# adc_chanels_b.net
KiCad netlist of a schematic drawn in Altium Designer
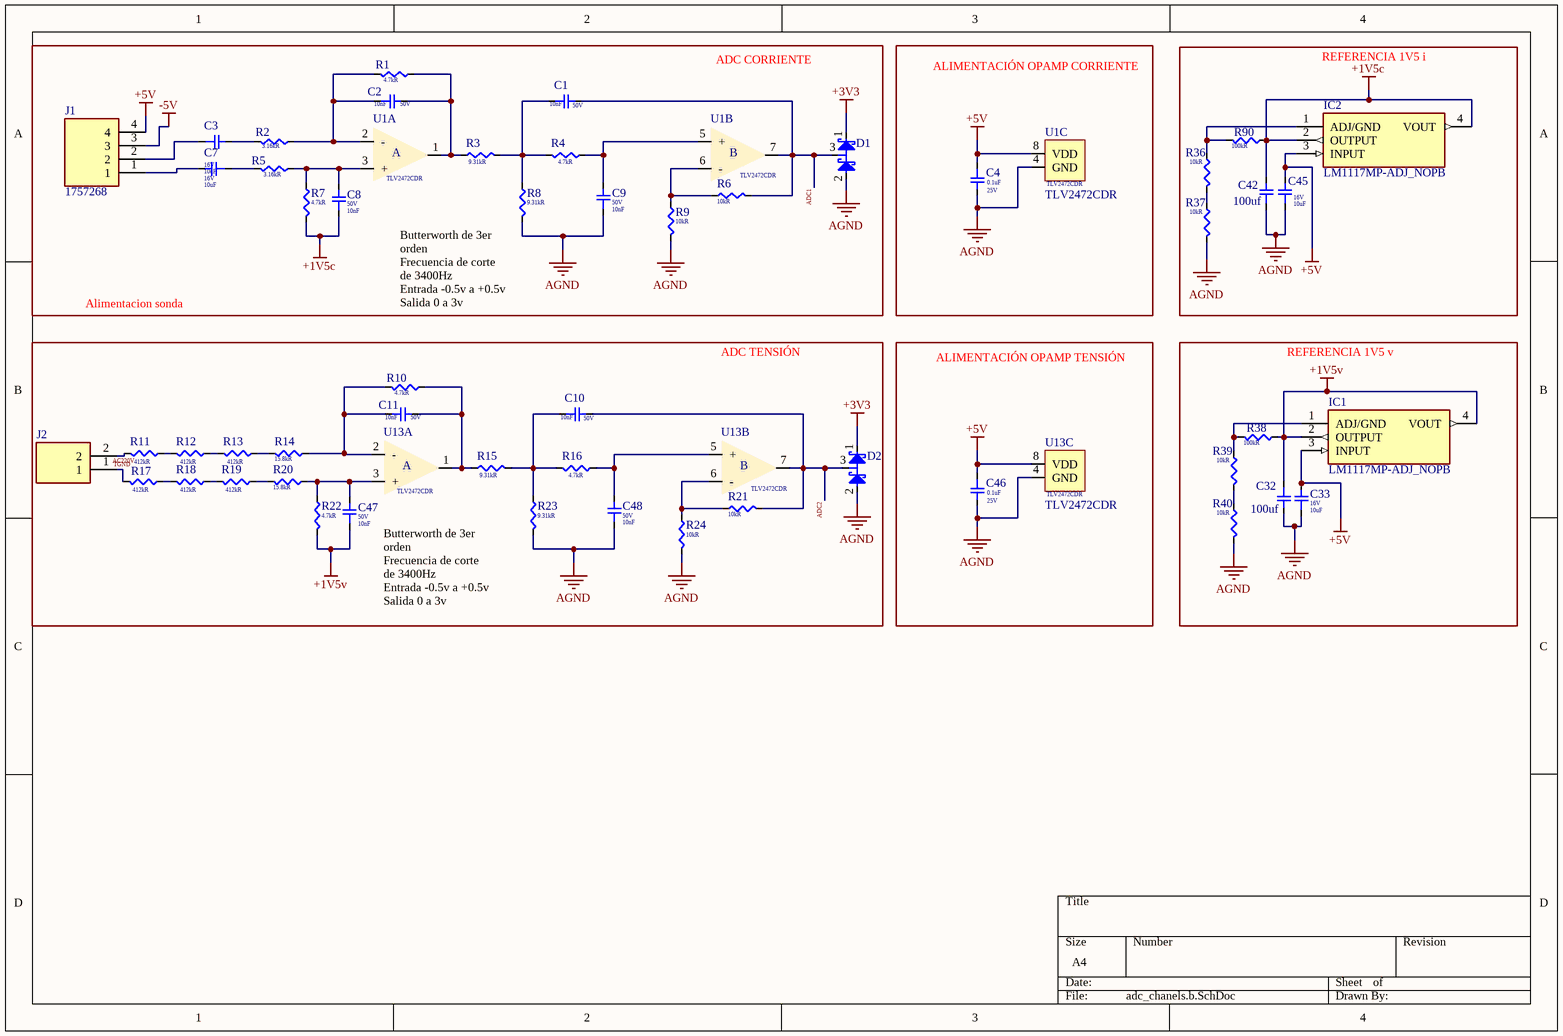
[diagram p0: adc_chanels.b.SchDoc]

(export (version "E")
  (design (tool "Eeschema 10.0.6"))
  (components
    (comp (ref "C1")
      (value "CAP_GRM2195C1H103FA01D_MURATA")
      (footprint "CAP smd 0805 ok")
      (description "0805 10 nF 50 V ±1% Tolerance C0G SMD Multilayer Ceramic Capacitor")
      (fields
        (field (name "TOLERANCE") "1%")
        (field (name "VOLTAGE") "50V")
        (field (name "CAPACITANCE") "10nF")
      )
      (libsource (lib "Cap") (part "CAP_GRM2195C1H103FA01D_MURATA"))
    )
    (comp (ref "C2")
      (value "CAP_GRM2195C1H103FA01D_MURATA")
      (footprint "CAP smd 0805 ok")
      (description "0805 10 nF 50 V ±1% Tolerance C0G SMD Multilayer Ceramic Capacitor")
      (fields
        (field (name "TOLERANCE") "1%")
        (field (name "VOLTAGE") "50V")
        (field (name "CAPACITANCE") "10nF")
      )
      (libsource (lib "Cap") (part "CAP_GRM2195C1H103FA01D_MURATA"))
    )
    (comp (ref "C3")
      (value "CAP_CL21A106KOCL3RC")
      (footprint "CAP smd 0805 OK")
      (description "CAP CER 10UF 16V X5R 0805")
      (fields
        (field (name "TOLERANCE") "10%")
        (field (name "VOLTAGE RATING") "16V")
        (field (name "CAPACITANCE") "10uF")
      )
      (libsource (lib "Cap") (part "CAP_CL21A106KOCL3RC"))
    )
    (comp (ref "C4")
      (value "CAP_CC0805KRX7R8BB104_YAGEO")
      (footprint "CAP smd 0805 ok")
      (description "CAPACITOR, 0805, 100NF, 25V, REEL 4000")
      (fields
        (field (name "TOLERANCE") "10%")
        (field (name "VOLTAGE RATING") "25V")
        (field (name "CAPACITANCE") "0.1uF")
      )
      (libsource (lib "Cap") (part "CAP_CC0805KRX7R8BB104_YAGEO"))
    )
    (comp (ref "C7")
      (value "CAP_CL21A106KOCL3RC")
      (footprint "CAP smd 0805 OK")
      (description "CAP CER 10UF 16V X5R 0805")
      (fields
        (field (name "TOLERANCE") "10%")
        (field (name "VOLTAGE RATING") "16V")
        (field (name "CAPACITANCE") "10uF")
      )
      (libsource (lib "Cap") (part "CAP_CL21A106KOCL3RC"))
    )
    (comp (ref "C8")
      (value "CAP_GRM2195C1H103FA01D_MURATA")
      (footprint "CAP smd 0805 ok")
      (description "0805 10 nF 50 V ±1% Tolerance C0G SMD Multilayer Ceramic Capacitor")
      (fields
        (field (name "TOLERANCE") "1%")
        (field (name "VOLTAGE") "50V")
        (field (name "CAPACITANCE") "10nF")
      )
      (libsource (lib "Cap") (part "CAP_GRM2195C1H103FA01D_MURATA"))
    )
    (comp (ref "C9")
      (value "CAP_GRM2195C1H103FA01D_MURATA")
      (footprint "CAP smd 0805 ok")
      (description "0805 10 nF 50 V ±1% Tolerance C0G SMD Multilayer Ceramic Capacitor")
      (fields
        (field (name "TOLERANCE") "1%")
        (field (name "VOLTAGE") "50V")
        (field (name "CAPACITANCE") "10nF")
      )
      (libsource (lib "Cap") (part "CAP_GRM2195C1H103FA01D_MURATA"))
    )
    (comp (ref "C10")
      (value "CAP_GRM2195C1H103FA01D_MURATA")
      (footprint "CAP smd 0805 ok")
      (description "0805 10 nF 50 V ±1% Tolerance C0G SMD Multilayer Ceramic Capacitor")
      (fields
        (field (name "TOLERANCE") "1%")
        (field (name "VOLTAGE") "50V")
        (field (name "CAPACITANCE") "10nF")
      )
      (libsource (lib "Cap") (part "CAP_GRM2195C1H103FA01D_MURATA"))
    )
    (comp (ref "C11")
      (value "CAP_GRM2195C1H103FA01D_MURATA")
      (footprint "CAP smd 0805 ok")
      (description "0805 10 nF 50 V ±1% Tolerance C0G SMD Multilayer Ceramic Capacitor")
      (fields
        (field (name "TOLERANCE") "1%")
        (field (name "VOLTAGE") "50V")
        (field (name "CAPACITANCE") "10nF")
      )
      (libsource (lib "Cap") (part "CAP_GRM2195C1H103FA01D_MURATA"))
    )
    (comp (ref "C32")
      (value "100uf")
      (footprint "Cap 100uf")
      (libsource (lib "Cap") (part "CAP 100uf murata"))
    )
    (comp (ref "C33")
      (value "CAP_CL21A106KOCL3RC")
      (footprint "CAP smd 0805 OK")
      (description "CAP CER 10UF 16V X5R 0805")
      (fields
        (field (name "TOLERANCE") "10%")
        (field (name "VOLTAGE RATING") "16V")
        (field (name "CAPACITANCE") "10uF")
      )
      (libsource (lib "Cap") (part "CAP_CL21A106KOCL3RC"))
    )
    (comp (ref "C42")
      (value "100uf")
      (footprint "Cap 100uf")
      (libsource (lib "Cap") (part "CAP 100uf murata"))
    )
    (comp (ref "C45")
      (value "CAP_CL21A106KOCL3RC")
      (footprint "CAP smd 0805 OK")
      (description "CAP CER 10UF 16V X5R 0805")
      (fields
        (field (name "TOLERANCE") "10%")
        (field (name "VOLTAGE RATING") "16V")
        (field (name "CAPACITANCE") "10uF")
      )
      (libsource (lib "Cap") (part "CAP_CL21A106KOCL3RC"))
    )
    (comp (ref "C46")
      (value "CAP_CC0805KRX7R8BB104_YAGEO")
      (footprint "CAP smd 0805 ok")
      (description "CAPACITOR, 0805, 100NF, 25V, REEL 4000")
      (fields
        (field (name "TOLERANCE") "10%")
        (field (name "VOLTAGE RATING") "25V")
        (field (name "CAPACITANCE") "0.1uF")
      )
      (libsource (lib "Cap") (part "CAP_CC0805KRX7R8BB104_YAGEO"))
    )
    (comp (ref "C47")
      (value "CAP_GRM2195C1H103FA01D_MURATA")
      (footprint "CAP smd 0805 ok")
      (description "0805 10 nF 50 V ±1% Tolerance C0G SMD Multilayer Ceramic Capacitor")
      (fields
        (field (name "TOLERANCE") "1%")
        (field (name "VOLTAGE") "50V")
        (field (name "CAPACITANCE") "10nF")
      )
      (libsource (lib "Cap") (part "CAP_GRM2195C1H103FA01D_MURATA"))
    )
    (comp (ref "C48")
      (value "CAP_GRM2195C1H103FA01D_MURATA")
      (footprint "CAP smd 0805 ok")
      (description "0805 10 nF 50 V ±1% Tolerance C0G SMD Multilayer Ceramic Capacitor")
      (fields
        (field (name "TOLERANCE") "1%")
        (field (name "VOLTAGE") "50V")
        (field (name "CAPACITANCE") "10nF")
      )
      (libsource (lib "Cap") (part "CAP_GRM2195C1H103FA01D_MURATA"))
    )
    (comp (ref "D1")
      (value "BAS40-04-TP")
      (footprint "diode shockit ok")
      (description "DIODE ARRAY SCHOTTKY 40V SOT23")
      (libsource (lib "diode") (part "BAS40-04-TP"))
    )
    (comp (ref "D2")
      (value "BAS40-04-TP")
      (footprint "diode shockit ok")
      (description "DIODE ARRAY SCHOTTKY 40V SOT23")
      (libsource (lib "diode") (part "BAS40-04-TP"))
    )
    (comp (ref "IC1")
      (value "LM1117MP-ADJ_NOPB")
      (footprint "SamacSys:SOT230P700X180-4N")
      (description "Integrated Circuit")
      (fields
        (field (name "MANUFACTURER_PART_NUMBER") "LM1117MP-ADJ/NOPB")
        (field (name "MOUSER PART NUMBER") "926-LM1117MP-ADJNOPB")
      )
      (libsource (lib "*") (part "LM1117MP-ADJ_NOPB"))
    )
    (comp (ref "IC2")
      (value "LM1117MP-ADJ_NOPB")
      (footprint "SamacSys:SOT230P700X180-4N")
      (description "Integrated Circuit")
      (fields
        (field (name "MANUFACTURER_PART_NUMBER") "LM1117MP-ADJ/NOPB")
        (field (name "MOUSER PART NUMBER") "926-LM1117MP-ADJNOPB")
      )
      (libsource (lib "*") (part "LM1117MP-ADJ_NOPB"))
    )
    (comp (ref "J1")
      (value "1757268")
      (footprint "SamacSys:1757268")
      (description "Connector")
      (fields (field (name "MOUSER PART NUMBER") "651-1757268"))
      (libsource (lib "*") (part "1757268"))
    )
    (comp (ref "J2")
      (value "1757242")
      (footprint "SamacSys:1757242")
      (description "Connector")
      (fields (field (name "MOUSER PART NUMBER") "651-1757242"))
      (libsource (lib "*") (part "1757242"))
    )
    (comp (ref "R1")
      (value "RC0805FR-074K7L")
      (footprint "res 0805 ok")
      (description "YAGEO - RC0805FR-074K7L - SMD  0805 [2012 Metric], 4.7 kohm,  125 mW")
      (fields (field (name "TOLERANCE") "1%") (field (name "RESISTANCE") "4.7kR"))
      (libsource (lib "res") (part "RC0805FR-074K7L"))
    )
    (comp (ref "R2")
      (value "RC0805FR-073K16L")
      (footprint "res 0805 ok")
      (description "Res Thick Film smd 0805 3.16K Ohm 1% 0.125W(1/8W)")
      (fields (field (name "TOLERANCE") "1%") (field (name "RESISTANCE") "3.16kR"))
      (libsource (lib "res") (part "RC0805FR-073K16L"))
    )
    (comp (ref "R3")
      (value "RC0805FR-079K31L")
      (footprint "res 0805 ok")
      (description "Res Thick Film smd 0805 9.31K Ohm 1% 0.125W(1/8W)")
      (fields (field (name "TOLERANCE") "1%") (field (name "RESISTANCE") "9.31kR"))
      (libsource (lib "res") (part "RC0805FR-079K31L"))
    )
    (comp (ref "R4")
      (value "RC0805FR-074K7L")
      (footprint "res 0805 ok")
      (description "YAGEO - RC0805FR-074K7L - SMD  0805 [2012 Metric], 4.7 kohm,  125 mW")
      (fields (field (name "TOLERANCE") "1%") (field (name "RESISTANCE") "4.7kR"))
      (libsource (lib "res") (part "RC0805FR-074K7L"))
    )
    (comp (ref "R5")
      (value "RC0805FR-073K16L")
      (footprint "res 0805 ok")
      (description "Res Thick Film smd 0805 3.16K Ohm 1% 0.125W(1/8W)")
      (fields (field (name "TOLERANCE") "1%") (field (name "RESISTANCE") "3.16kR"))
      (libsource (lib "res") (part "RC0805FR-073K16L"))
    )
    (comp (ref "R6")
      (value "RC0805FR-0710KL")
      (footprint "res 0805 ok")
      (description "RES SMD  0805 10K OHM 1% 1/8W")
      (fields (field (name "TOLERANCE") "1%") (field (name "RESISTANCE") "10kR"))
      (libsource (lib "res") (part "RC0805FR-0710KL"))
    )
    (comp (ref "R7")
      (value "RC0805FR-074K7L")
      (footprint "res 0805 ok")
      (description "YAGEO - RC0805FR-074K7L - SMD  0805 [2012 Metric], 4.7 kohm,  125 mW")
      (fields (field (name "TOLERANCE") "1%") (field (name "RESISTANCE") "4.7kR"))
      (libsource (lib "res") (part "RC0805FR-074K7L"))
    )
    (comp (ref "R8")
      (value "RC0805FR-079K31L")
      (footprint "res 0805 ok")
      (description "Res Thick Film smd 0805 9.31K Ohm 1% 0.125W(1/8W)")
      (fields (field (name "TOLERANCE") "1%") (field (name "RESISTANCE") "9.31kR"))
      (libsource (lib "res") (part "RC0805FR-079K31L"))
    )
    (comp (ref "R9")
      (value "RC0805FR-0710KL")
      (footprint "res 0805 ok")
      (description "RES SMD  0805 10K OHM 1% 1/8W")
      (fields (field (name "TOLERANCE") "1%") (field (name "RESISTANCE") "10kR"))
      (libsource (lib "res") (part "RC0805FR-0710KL"))
    )
    (comp (ref "R10")
      (value "RC0805FR-074K7L")
      (footprint "res 0805 ok")
      (description "YAGEO - RC0805FR-074K7L - SMD  0805 [2012 Metric], 4.7 kohm,  125 mW")
      (fields (field (name "TOLERANCE") "1%") (field (name "RESISTANCE") "4.7kR"))
      (libsource (lib "res") (part "RC0805FR-074K7L"))
    )
    (comp (ref "R11")
      (value "RC0805FR-07412KL")
      (footprint "res 0805 ok")
      (description "RES SMD 0805 412K OHM 1% 1/8W")
      (fields (field (name "TOLERANCE") "1%") (field (name "RESISTANCE") "412kR"))
      (libsource (lib "res") (part "RC0805FR-07412KL"))
    )
    (comp (ref "R12")
      (value "RC0805FR-07412KL")
      (footprint "res 0805 ok")
      (description "RES SMD 0805 412K OHM 1% 1/8W")
      (fields (field (name "TOLERANCE") "1%") (field (name "RESISTANCE") "412kR"))
      (libsource (lib "res") (part "RC0805FR-07412KL"))
    )
    (comp (ref "R13")
      (value "RC0805FR-07412KL")
      (footprint "res 0805 ok")
      (description "RES SMD 0805 412K OHM 1% 1/8W")
      (fields (field (name "TOLERANCE") "1%") (field (name "RESISTANCE") "412kR"))
      (libsource (lib "res") (part "RC0805FR-07412KL"))
    )
    (comp (ref "R14")
      (value "RC0805FR-0715K8L")
      (footprint "res 0805 ok")
      (description "Res Thick Film smd 0805 15.8K Ohm 1% 0.125W(1/8W)")
      (fields (field (name "TOLERANCE") "1%") (field (name "RESISTANCE") "15.8kR"))
      (libsource (lib "res") (part "RC0805FR-0715K8L"))
    )
    (comp (ref "R15")
      (value "RC0805FR-079K31L")
      (footprint "res 0805 ok")
      (description "Res Thick Film smd 0805 9.31K Ohm 1% 0.125W(1/8W)")
      (fields (field (name "TOLERANCE") "1%") (field (name "RESISTANCE") "9.31kR"))
      (libsource (lib "res") (part "RC0805FR-079K31L"))
    )
    (comp (ref "R16")
      (value "RC0805FR-074K7L")
      (footprint "res 0805 ok")
      (description "YAGEO - RC0805FR-074K7L - SMD  0805 [2012 Metric], 4.7 kohm,  125 mW")
      (fields (field (name "TOLERANCE") "1%") (field (name "RESISTANCE") "4.7kR"))
      (libsource (lib "res") (part "RC0805FR-074K7L"))
    )
    (comp (ref "R17")
      (value "RC0805FR-07412KL")
      (footprint "res 0805 ok")
      (description "RES SMD 0805 412K OHM 1% 1/8W")
      (fields (field (name "TOLERANCE") "1%") (field (name "RESISTANCE") "412kR"))
      (libsource (lib "res") (part "RC0805FR-07412KL"))
    )
    (comp (ref "R18")
      (value "RC0805FR-07412KL")
      (footprint "res 0805 ok")
      (description "RES SMD 0805 412K OHM 1% 1/8W")
      (fields (field (name "TOLERANCE") "1%") (field (name "RESISTANCE") "412kR"))
      (libsource (lib "res") (part "RC0805FR-07412KL"))
    )
    (comp (ref "R19")
      (value "RC0805FR-07412KL")
      (footprint "res 0805 ok")
      (description "RES SMD 0805 412K OHM 1% 1/8W")
      (fields (field (name "TOLERANCE") "1%") (field (name "RESISTANCE") "412kR"))
      (libsource (lib "res") (part "RC0805FR-07412KL"))
    )
    (comp (ref "R20")
      (value "RC0805FR-0715K8L")
      (footprint "res 0805 ok")
      (description "Res Thick Film smd 0805 15.8K Ohm 1% 0.125W(1/8W)")
      (fields (field (name "TOLERANCE") "1%") (field (name "RESISTANCE") "15.8kR"))
      (libsource (lib "res") (part "RC0805FR-0715K8L"))
    )
    (comp (ref "R21")
      (value "RC0805FR-0710KL")
      (footprint "res 0805 ok")
      (description "RES SMD  0805 10K OHM 1% 1/8W")
      (fields (field (name "TOLERANCE") "1%") (field (name "RESISTANCE") "10kR"))
      (libsource (lib "res") (part "RC0805FR-0710KL"))
    )
    (comp (ref "R22")
      (value "RC0805FR-074K7L")
      (footprint "res 0805 ok")
      (description "YAGEO - RC0805FR-074K7L - SMD  0805 [2012 Metric], 4.7 kohm,  125 mW")
      (fields (field (name "TOLERANCE") "1%") (field (name "RESISTANCE") "4.7kR"))
      (libsource (lib "res") (part "RC0805FR-074K7L"))
    )
    (comp (ref "R23")
      (value "RC0805FR-079K31L")
      (footprint "res 0805 ok")
      (description "Res Thick Film smd 0805 9.31K Ohm 1% 0.125W(1/8W)")
      (fields (field (name "TOLERANCE") "1%") (field (name "RESISTANCE") "9.31kR"))
      (libsource (lib "res") (part "RC0805FR-079K31L"))
    )
    (comp (ref "R24")
      (value "RC0805FR-0710KL")
      (footprint "res 0805 ok")
      (description "RES SMD  0805 10K OHM 1% 1/8W")
      (fields (field (name "TOLERANCE") "1%") (field (name "RESISTANCE") "10kR"))
      (libsource (lib "res") (part "RC0805FR-0710KL"))
    )
    (comp (ref "R36")
      (value "RC0805JR-0710KL")
      (footprint "res 0805 ok")
      (description "Res Thick Film smd 0805 10K Ohm 5% 1/8W")
      (fields (field (name "TOLERANCE") "5%") (field (name "RESISTANCE") "10kR"))
      (libsource (lib "res") (part "RC0805JR-0710KL"))
    )
    (comp (ref "R37")
      (value "RC0805JR-0710KL")
      (footprint "res 0805 ok")
      (description "Res Thick Film smd 0805 10K Ohm 5% 1/8W")
      (fields (field (name "TOLERANCE") "5%") (field (name "RESISTANCE") "10kR"))
      (libsource (lib "res") (part "RC0805JR-0710KL"))
    )
    (comp (ref "R38")
      (value "AC0805JR-07100KL")
      (footprint "res 0805 ok")
      (description "Thick Film Resistors - SMD 0805  100K ohm 5% 1/8W")
      (fields (field (name "TOLERANCE") "5%") (field (name "RESISTANCE") "100kR"))
      (libsource (lib "res") (part "AC0805JR-07100KL"))
    )
    (comp (ref "R39")
      (value "RC0805JR-0710KL")
      (footprint "res 0805 ok")
      (description "Res Thick Film smd 0805 10K Ohm 5% 1/8W")
      (fields (field (name "TOLERANCE") "5%") (field (name "RESISTANCE") "10kR"))
      (libsource (lib "res") (part "RC0805JR-0710KL"))
    )
    (comp (ref "R40")
      (value "RC0805JR-0710KL")
      (footprint "res 0805 ok")
      (description "Res Thick Film smd 0805 10K Ohm 5% 1/8W")
      (fields (field (name "TOLERANCE") "5%") (field (name "RESISTANCE") "10kR"))
      (libsource (lib "res") (part "RC0805JR-0710KL"))
    )
    (comp (ref "R90")
      (value "AC0805JR-07100KL")
      (footprint "res 0805 ok")
      (description "Thick Film Resistors - SMD 0805  100K ohm 5% 1/8W")
      (fields (field (name "TOLERANCE") "5%") (field (name "RESISTANCE") "100kR"))
      (libsource (lib "res") (part "AC0805JR-07100KL"))
    )
    (comp (ref "U1")
      (value "TLV2472CDR")
      (footprint "tlv2472 ok")
      (description "IC OPAMP GP 2.8MHZ RRO 8SOIC")
      (libsource (lib "ic") (part "TLV2472CDR"))
    )
    (comp (ref "U13")
      (value "TLV2472CDR")
      (footprint "tlv2472 ok")
      (description "IC OPAMP GP 2.8MHZ RRO 8SOIC")
      (libsource (lib "ic") (part "TLV2472CDR"))
    )
  )
  (nets
    (net (code "1") (name "+1V5c") (class "Default")
      (node (ref "C42") (pin "23") (pinfunction "23_23") (pintype "passive"))
      (node (ref "C8") (pin "23") (pinfunction "23_23") (pintype "passive"))
      (node (ref "IC2") (pin "2") (pinfunction "OUTPUT_2") (pintype "output"))
      (node (ref "IC2") (pin "4") (pinfunction "VOUT_4") (pintype "output"))
      (node (ref "R7") (pin "2") (pinfunction "2_2") (pintype "passive"))
      (node (ref "R90") (pin "1") (pinfunction "1_1") (pintype "passive"))
    )
    (net (code "2") (name "+1V5v") (class "Default")
      (node (ref "C32") (pin "22") (pinfunction "22_22") (pintype "passive"))
      (node (ref "C47") (pin "23") (pinfunction "23_23") (pintype "passive"))
      (node (ref "IC1") (pin "2") (pinfunction "OUTPUT_2") (pintype "output"))
      (node (ref "IC1") (pin "4") (pinfunction "VOUT_4") (pintype "output"))
      (node (ref "R22") (pin "2") (pinfunction "2_2") (pintype "passive"))
      (node (ref "R38") (pin "1") (pinfunction "1_1") (pintype "passive"))
    )
    (net (code "3") (name "+3V3") (class "Default")
      (node (ref "D1") (pin "1") (pinfunction "1_1") (pintype "passive"))
      (node (ref "D2") (pin "1") (pinfunction "1_1") (pintype "passive"))
    )
    (net (code "4") (name "+5V") (class "Default")
      (node (ref "C33") (pin "22") (pinfunction "22_22") (pintype "passive"))
      (node (ref "C4") (pin "23") (pinfunction "23_23") (pintype "passive"))
      (node (ref "C45") (pin "22") (pinfunction "22_22") (pintype "passive"))
      (node (ref "C46") (pin "23") (pinfunction "23_23") (pintype "passive"))
      (node (ref "IC1") (pin "3") (pinfunction "INPUT_3") (pintype "input"))
      (node (ref "IC2") (pin "3") (pinfunction "INPUT_3") (pintype "input"))
      (node (ref "J1") (pin "4") (pinfunction "4_4") (pintype "passive"))
      (node (ref "U1") (pin "8") (pinfunction "VDD_8") (pintype "passive"))
      (node (ref "U13") (pin "8") (pinfunction "VDD_8") (pintype "passive"))
    )
    (net (code "5") (name "-5V") (class "Default")
      (node (ref "J1") (pin "3") (pinfunction "3_3") (pintype "passive"))
    )
    (net (code "6") (name "/AC220V") (class "Default")
      (node (ref "J2") (pin "2") (pinfunction "2_2") (pintype "passive"))
      (node (ref "R11") (pin "2") (pinfunction "2_2") (pintype "passive"))
    )
    (net (code "7") (name "/ADC1") (class "Default")
      (node (ref "C1") (pin "22") (pinfunction "22_22") (pintype "passive"))
      (node (ref "D1") (pin "3") (pinfunction "3_3") (pintype "passive"))
      (node (ref "R6") (pin "2") (pinfunction "2_2") (pintype "passive"))
      (node (ref "U1") (pin "7") (pinfunction "7_7") (pintype "passive"))
    )
    (net (code "8") (name "/ADC2") (class "Default")
      (node (ref "C10") (pin "22") (pinfunction "22_22") (pintype "passive"))
      (node (ref "D2") (pin "3") (pinfunction "3_3") (pintype "passive"))
      (node (ref "R21") (pin "2") (pinfunction "2_2") (pintype "passive"))
      (node (ref "U13") (pin "7") (pinfunction "7_7") (pintype "passive"))
    )
    (net (code "9") (name "/TGND") (class "Default")
      (node (ref "J2") (pin "1") (pinfunction "1_1") (pintype "passive"))
      (node (ref "R17") (pin "2") (pinfunction "2_2") (pintype "passive"))
    )
    (net (code "10") (name "AGND") (class "Default")
      (node (ref "C32") (pin "23") (pinfunction "23_23") (pintype "passive"))
      (node (ref "C33") (pin "23") (pinfunction "23_23") (pintype "passive"))
      (node (ref "C4") (pin "22") (pinfunction "22_22") (pintype "passive"))
      (node (ref "C42") (pin "22") (pinfunction "22_22") (pintype "passive"))
      (node (ref "C45") (pin "23") (pinfunction "23_23") (pintype "passive"))
      (node (ref "C46") (pin "22") (pinfunction "22_22") (pintype "passive"))
      (node (ref "C48") (pin "23") (pinfunction "23_23") (pintype "passive"))
      (node (ref "C9") (pin "23") (pinfunction "23_23") (pintype "passive"))
      (node (ref "D1") (pin "2") (pinfunction "2_2") (pintype "passive"))
      (node (ref "D2") (pin "2") (pinfunction "2_2") (pintype "passive"))
      (node (ref "R23") (pin "2") (pinfunction "2_2") (pintype "passive"))
      (node (ref "R24") (pin "2") (pinfunction "2_2") (pintype "passive"))
      (node (ref "R37") (pin "1") (pintype "passive"))
      (node (ref "R40") (pin "1") (pintype "passive"))
      (node (ref "R8") (pin "2") (pinfunction "2_2") (pintype "passive"))
      (node (ref "R9") (pin "2") (pinfunction "2_2") (pintype "passive"))
      (node (ref "U1") (pin "4") (pinfunction "GND_4") (pintype "passive"))
      (node (ref "U13") (pin "4") (pinfunction "GND_4") (pintype "passive"))
    )
    (net (code "11") (name "Net-(C1-Pad23)") (class "Default")
      (node (ref "C1") (pin "23") (pinfunction "23_23") (pintype "passive"))
      (node (ref "R3") (pin "2") (pinfunction "2_2") (pintype "passive"))
      (node (ref "R4") (pin "2") (pinfunction "2_2") (pintype "passive"))
      (node (ref "R8") (pin "1") (pinfunction "1_1") (pintype "passive"))
    )
    (net (code "12") (name "Net-(C2-Pad22)") (class "Default")
      (node (ref "C2") (pin "22") (pinfunction "22_22") (pintype "passive"))
      (node (ref "R1") (pin "1") (pinfunction "1_1") (pintype "passive"))
      (node (ref "R3") (pin "1") (pinfunction "1_1") (pintype "passive"))
      (node (ref "U1") (pin "1") (pinfunction "1_1") (pintype "passive"))
    )
    (net (code "13") (name "Net-(C3-Pad22)") (class "Default")
      (node (ref "C3") (pin "22") (pinfunction "22_22") (pintype "passive"))
      (node (ref "R2") (pin "1") (pinfunction "1_1") (pintype "passive"))
    )
    (net (code "14") (name "Net-(C3-Pad23)") (class "Default")
      (node (ref "C3") (pin "23") (pinfunction "23_23") (pintype "passive"))
      (node (ref "J1") (pin "2") (pinfunction "2_2") (pintype "passive"))
    )
    (net (code "15") (name "Net-(C7-Pad22)") (class "Default")
      (node (ref "C7") (pin "22") (pinfunction "22_22") (pintype "passive"))
      (node (ref "J1") (pin "1") (pinfunction "1_1") (pintype "passive"))
    )
    (net (code "16") (name "Net-(C7-Pad23)") (class "Default")
      (node (ref "C7") (pin "23") (pinfunction "23_23") (pintype "passive"))
      (node (ref "R5") (pin "1") (pinfunction "1_1") (pintype "passive"))
    )
    (net (code "17") (name "Net-(C10-Pad23)") (class "Default")
      (node (ref "C10") (pin "23") (pinfunction "23_23") (pintype "passive"))
      (node (ref "R15") (pin "2") (pinfunction "2_2") (pintype "passive"))
      (node (ref "R16") (pin "2") (pinfunction "2_2") (pintype "passive"))
      (node (ref "R23") (pin "1") (pinfunction "1_1") (pintype "passive"))
    )
    (net (code "18") (name "Net-(C11-Pad22)") (class "Default")
      (node (ref "C11") (pin "22") (pinfunction "22_22") (pintype "passive"))
      (node (ref "R10") (pin "1") (pinfunction "1_1") (pintype "passive"))
      (node (ref "R15") (pin "1") (pinfunction "1_1") (pintype "passive"))
      (node (ref "U13") (pin "1") (pinfunction "1_1") (pintype "passive"))
    )
    (net (code "19") (name "Net-(IC1-ADJ{slash}GND)") (class "Default")
      (node (ref "IC1") (pin "1") (pinfunction "ADJ/GND_1") (pintype "power_in"))
      (node (ref "R38") (pin "2") (pinfunction "2_2") (pintype "passive"))
      (node (ref "R39") (pin "2") (pinfunction "2_2") (pintype "passive"))
    )
    (net (code "20") (name "Net-(IC2-ADJ{slash}GND)") (class "Default")
      (node (ref "IC2") (pin "1") (pinfunction "ADJ/GND_1") (pintype "power_in"))
      (node (ref "R36") (pin "2") (pinfunction "2_2") (pintype "passive"))
      (node (ref "R90") (pin "2") (pinfunction "2_2") (pintype "passive"))
    )
    (net (code "21") (name "Net-(R11-Pad1)") (class "Default")
      (node (ref "R11") (pin "1") (pinfunction "1_1") (pintype "passive"))
      (node (ref "R12") (pin "2") (pinfunction "2_2") (pintype "passive"))
    )
    (net (code "22") (name "Net-(R12-Pad1)") (class "Default")
      (node (ref "R12") (pin "1") (pinfunction "1_1") (pintype "passive"))
      (node (ref "R13") (pin "2") (pinfunction "2_2") (pintype "passive"))
    )
    (net (code "23") (name "Net-(R13-Pad1)") (class "Default")
      (node (ref "R13") (pin "1") (pinfunction "1_1") (pintype "passive"))
      (node (ref "R14") (pin "2") (pinfunction "2_2") (pintype "passive"))
    )
    (net (code "24") (name "Net-(R17-Pad1)") (class "Default")
      (node (ref "R17") (pin "1") (pinfunction "1_1") (pintype "passive"))
      (node (ref "R18") (pin "2") (pinfunction "2_2") (pintype "passive"))
    )
    (net (code "25") (name "Net-(R18-Pad1)") (class "Default")
      (node (ref "R18") (pin "1") (pinfunction "1_1") (pintype "passive"))
      (node (ref "R19") (pin "2") (pinfunction "2_2") (pintype "passive"))
    )
    (net (code "26") (name "Net-(R19-Pad1)") (class "Default")
      (node (ref "R19") (pin "1") (pinfunction "1_1") (pintype "passive"))
      (node (ref "R20") (pin "2") (pinfunction "2_2") (pintype "passive"))
    )
    (net (code "27") (name "Net-(R36-Pad1)") (class "Default")
      (node (ref "R36") (pin "1") (pintype "passive"))
      (node (ref "R37") (pin "2") (pinfunction "2_2") (pintype "passive"))
    )
    (net (code "28") (name "Net-(R39-Pad1)") (class "Default")
      (node (ref "R39") (pin "1") (pintype "passive"))
      (node (ref "R40") (pin "2") (pinfunction "2_2") (pintype "passive"))
    )
    (net (code "29") (name "Net-(U1A-+)") (class "Default")
      (node (ref "C8") (pin "22") (pinfunction "22_22") (pintype "passive"))
      (node (ref "R5") (pin "2") (pinfunction "2_2") (pintype "passive"))
      (node (ref "R7") (pin "1") (pinfunction "1_1") (pintype "passive"))
      (node (ref "U1") (pin "3") (pinfunction "+_3") (pintype "passive"))
    )
    (net (code "30") (name "Net-(U1A--)") (class "Default")
      (node (ref "C2") (pin "23") (pinfunction "23_23") (pintype "passive"))
      (node (ref "R1") (pin "2") (pinfunction "2_2") (pintype "passive"))
      (node (ref "R2") (pin "2") (pinfunction "2_2") (pintype "passive"))
      (node (ref "U1") (pin "2") (pinfunction "-_2") (pintype "passive"))
    )
    (net (code "31") (name "Net-(U1B-+)") (class "Default")
      (node (ref "C9") (pin "22") (pinfunction "22_22") (pintype "passive"))
      (node (ref "R4") (pin "1") (pinfunction "1_1") (pintype "passive"))
      (node (ref "U1") (pin "5") (pinfunction "+_5") (pintype "passive"))
    )
    (net (code "32") (name "Net-(U1B--)") (class "Default")
      (node (ref "R6") (pin "1") (pinfunction "1_1") (pintype "passive"))
      (node (ref "R9") (pin "1") (pinfunction "1_1") (pintype "passive"))
      (node (ref "U1") (pin "6") (pinfunction "-_6") (pintype "passive"))
    )
    (net (code "33") (name "Net-(U13A-+)") (class "Default")
      (node (ref "C47") (pin "22") (pinfunction "22_22") (pintype "passive"))
      (node (ref "R20") (pin "1") (pinfunction "1_1") (pintype "passive"))
      (node (ref "R22") (pin "1") (pinfunction "1_1") (pintype "passive"))
      (node (ref "U13") (pin "3") (pinfunction "+_3") (pintype "passive"))
    )
    (net (code "34") (name "Net-(U13A--)") (class "Default")
      (node (ref "C11") (pin "23") (pinfunction "23_23") (pintype "passive"))
      (node (ref "R10") (pin "2") (pinfunction "2_2") (pintype "passive"))
      (node (ref "R14") (pin "1") (pinfunction "1_1") (pintype "passive"))
      (node (ref "U13") (pin "2") (pinfunction "-_2") (pintype "passive"))
    )
    (net (code "35") (name "Net-(U13B-+)") (class "Default")
      (node (ref "C48") (pin "22") (pinfunction "22_22") (pintype "passive"))
      (node (ref "R16") (pin "1") (pinfunction "1_1") (pintype "passive"))
      (node (ref "U13") (pin "5") (pinfunction "+_5") (pintype "passive"))
    )
    (net (code "36") (name "Net-(U13B--)") (class "Default")
      (node (ref "R21") (pin "1") (pinfunction "1_1") (pintype "passive"))
      (node (ref "R24") (pin "1") (pinfunction "1_1") (pintype "passive"))
      (node (ref "U13") (pin "6") (pinfunction "-_6") (pintype "passive"))
    )
  )
)
